# M206.net
KiCad netlist of a schematic drawn in EAGLE
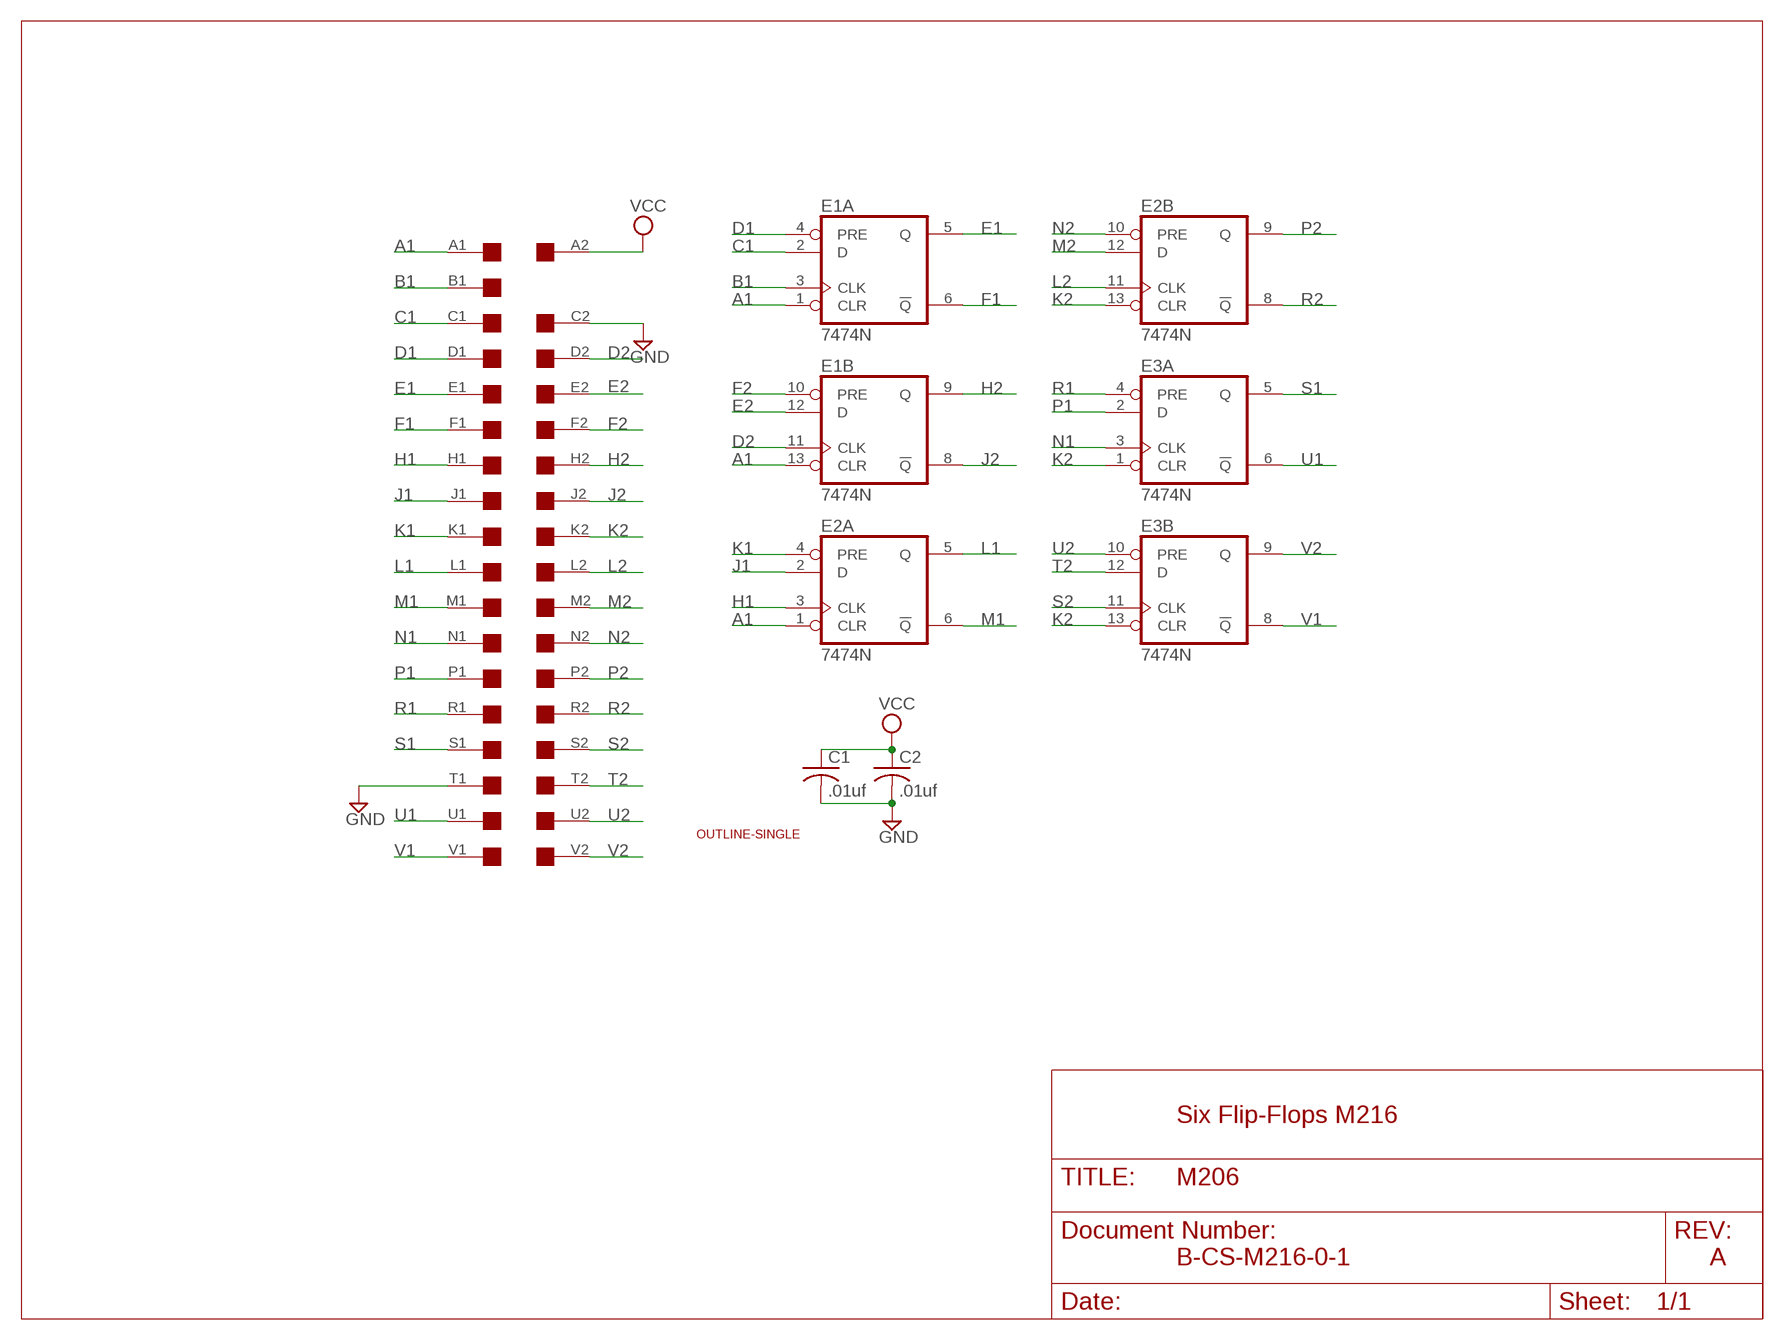
[diagram p0: schematic, sheet 1]

(export (version "E")
  (design (tool "Eeschema 10.0.6"))
  (components
    (comp (ref "C1")
      (value ".01uf")
      (footprint "eagle-import:C050-025X075")
      (libsource (lib "eagle-import") (part "C-US050-025X075"))
    )
    (comp (ref "C2")
      (value ".01uf")
      (footprint "eagle-import:C050-025X075")
      (libsource (lib "eagle-import") (part "C-US050-025X075"))
    )
    (comp (ref "E1")
      (value "7474N")
      (footprint "eagle-import:DIL14")
      (libsource (lib "eagle-import") (part "7474NS"))
    )
    (comp (ref "E2")
      (value "7474N")
      (footprint "eagle-import:DIL14")
      (libsource (lib "eagle-import") (part "7474NS"))
    )
    (comp (ref "E3")
      (value "7474N")
      (footprint "eagle-import:DIL14")
      (libsource (lib "eagle-import") (part "7474NS"))
    )
    (comp (ref "U$1")
      (value "OUTLINE-SINGLE")
      (footprint "eagle-import:SINGLE")
      (libsource (lib "eagle-import") (part "OUTLINE-SINGLE"))
    )
    (comp (ref "U$4")
      (value "SINGLE")
      (footprint "eagle-import:EDGE-CON2")
      (libsource (lib "eagle-import") (part "SINGLE"))
    )
  )
  (nets
    (net (code "1") (name "/A1") (class "Default")
      (node (ref "E1") (pin "1") (pinfunction "CLR_1") (pintype "input"))
      (node (ref "E1") (pin "13") (pinfunction "CLR_13") (pintype "input"))
      (node (ref "E2") (pin "1") (pinfunction "CLR_1") (pintype "input"))
      (node (ref "U$4") (pin "A1") (pinfunction "1_A1") (pintype "bidirectional"))
    )
    (net (code "2") (name "/B1") (class "Default")
      (node (ref "E1") (pin "3") (pinfunction "CLK_3") (pintype "input"))
      (node (ref "U$4") (pin "B1") (pinfunction "1_B1") (pintype "bidirectional"))
    )
    (net (code "3") (name "/C1") (class "Default")
      (node (ref "E1") (pin "2") (pinfunction "D_2") (pintype "input"))
      (node (ref "U$4") (pin "C1") (pinfunction "1_C1") (pintype "bidirectional"))
    )
    (net (code "4") (name "/D1") (class "Default")
      (node (ref "E1") (pin "4") (pinfunction "PRE_4") (pintype "input"))
      (node (ref "U$4") (pin "D1") (pinfunction "1_D1") (pintype "bidirectional"))
    )
    (net (code "5") (name "/D2") (class "Default")
      (node (ref "E1") (pin "11") (pinfunction "CLK_11") (pintype "input"))
      (node (ref "U$4") (pin "D2") (pinfunction "1_D2") (pintype "bidirectional"))
    )
    (net (code "6") (name "/E1") (class "Default")
      (node (ref "E1") (pin "5") (pinfunction "Q_5") (pintype "output"))
      (node (ref "U$4") (pin "E1") (pinfunction "1_E1") (pintype "bidirectional"))
    )
    (net (code "7") (name "/E2") (class "Default")
      (node (ref "E1") (pin "12") (pinfunction "D_12") (pintype "input"))
      (node (ref "U$4") (pin "E2") (pinfunction "1_E2") (pintype "bidirectional"))
    )
    (net (code "8") (name "/F1") (class "Default")
      (node (ref "E1") (pin "6") (pinfunction "~{Q}_6") (pintype "output"))
      (node (ref "U$4") (pin "F1") (pinfunction "1_F1") (pintype "bidirectional"))
    )
    (net (code "9") (name "/F2") (class "Default")
      (node (ref "E1") (pin "10") (pinfunction "PRE_10") (pintype "input"))
      (node (ref "U$4") (pin "F2") (pinfunction "1_F2") (pintype "bidirectional"))
    )
    (net (code "10") (name "/H1") (class "Default")
      (node (ref "E2") (pin "3") (pinfunction "CLK_3") (pintype "input"))
      (node (ref "U$4") (pin "H1") (pinfunction "1_H1") (pintype "bidirectional"))
    )
    (net (code "11") (name "/H2") (class "Default")
      (node (ref "E1") (pin "9") (pinfunction "Q_9") (pintype "output"))
      (node (ref "U$4") (pin "H2") (pinfunction "1_H2") (pintype "bidirectional"))
    )
    (net (code "12") (name "/J1") (class "Default")
      (node (ref "E2") (pin "2") (pinfunction "D_2") (pintype "input"))
      (node (ref "U$4") (pin "J1") (pinfunction "1_J1") (pintype "bidirectional"))
    )
    (net (code "13") (name "/J2") (class "Default")
      (node (ref "E1") (pin "8") (pinfunction "~{Q}_8") (pintype "output"))
      (node (ref "U$4") (pin "J2") (pinfunction "1_J2") (pintype "bidirectional"))
    )
    (net (code "14") (name "/K1") (class "Default")
      (node (ref "E2") (pin "4") (pinfunction "PRE_4") (pintype "input"))
      (node (ref "U$4") (pin "K1") (pinfunction "1_K1") (pintype "bidirectional"))
    )
    (net (code "15") (name "/K2") (class "Default")
      (node (ref "E2") (pin "13") (pinfunction "CLR_13") (pintype "input"))
      (node (ref "E3") (pin "1") (pinfunction "CLR_1") (pintype "input"))
      (node (ref "E3") (pin "13") (pinfunction "CLR_13") (pintype "input"))
      (node (ref "U$4") (pin "K2") (pinfunction "1_K2") (pintype "bidirectional"))
    )
    (net (code "16") (name "/L1") (class "Default")
      (node (ref "E2") (pin "5") (pinfunction "Q_5") (pintype "output"))
      (node (ref "U$4") (pin "L1") (pinfunction "1_L1") (pintype "bidirectional"))
    )
    (net (code "17") (name "/L2") (class "Default")
      (node (ref "E2") (pin "11") (pinfunction "CLK_11") (pintype "input"))
      (node (ref "U$4") (pin "L2") (pinfunction "1_L2") (pintype "bidirectional"))
    )
    (net (code "18") (name "/M1") (class "Default")
      (node (ref "E2") (pin "6") (pinfunction "~{Q}_6") (pintype "output"))
      (node (ref "U$4") (pin "M1") (pinfunction "1_M1") (pintype "bidirectional"))
    )
    (net (code "19") (name "/M2") (class "Default")
      (node (ref "E2") (pin "12") (pinfunction "D_12") (pintype "input"))
      (node (ref "U$4") (pin "M2") (pinfunction "1_M2") (pintype "bidirectional"))
    )
    (net (code "20") (name "/N1") (class "Default")
      (node (ref "E3") (pin "3") (pinfunction "CLK_3") (pintype "input"))
      (node (ref "U$4") (pin "N1") (pinfunction "1_N1") (pintype "bidirectional"))
    )
    (net (code "21") (name "/N2") (class "Default")
      (node (ref "E2") (pin "10") (pinfunction "PRE_10") (pintype "input"))
      (node (ref "U$4") (pin "N2") (pinfunction "1_N2") (pintype "bidirectional"))
    )
    (net (code "22") (name "/P1") (class "Default")
      (node (ref "E3") (pin "2") (pinfunction "D_2") (pintype "input"))
      (node (ref "U$4") (pin "P1") (pinfunction "1_P1") (pintype "bidirectional"))
    )
    (net (code "23") (name "/P2") (class "Default")
      (node (ref "E2") (pin "9") (pinfunction "Q_9") (pintype "output"))
      (node (ref "U$4") (pin "P2") (pinfunction "1_P2") (pintype "bidirectional"))
    )
    (net (code "24") (name "/R1") (class "Default")
      (node (ref "E3") (pin "4") (pinfunction "PRE_4") (pintype "input"))
      (node (ref "U$4") (pin "R1") (pinfunction "1_R1") (pintype "bidirectional"))
    )
    (net (code "25") (name "/R2") (class "Default")
      (node (ref "E2") (pin "8") (pinfunction "~{Q}_8") (pintype "output"))
      (node (ref "U$4") (pin "R2") (pinfunction "1_R2") (pintype "bidirectional"))
    )
    (net (code "26") (name "/S1") (class "Default")
      (node (ref "E3") (pin "5") (pinfunction "Q_5") (pintype "output"))
      (node (ref "U$4") (pin "S1") (pinfunction "1_S1") (pintype "bidirectional"))
    )
    (net (code "27") (name "/S2") (class "Default")
      (node (ref "E3") (pin "11") (pinfunction "CLK_11") (pintype "input"))
      (node (ref "U$4") (pin "S2") (pinfunction "1_S2") (pintype "bidirectional"))
    )
    (net (code "28") (name "/T2") (class "Default")
      (node (ref "E3") (pin "12") (pinfunction "D_12") (pintype "input"))
      (node (ref "U$4") (pin "T2") (pinfunction "1_T2") (pintype "bidirectional"))
    )
    (net (code "29") (name "/U1") (class "Default")
      (node (ref "E3") (pin "6") (pinfunction "~{Q}_6") (pintype "output"))
      (node (ref "U$4") (pin "U1") (pinfunction "1_U1") (pintype "bidirectional"))
    )
    (net (code "30") (name "/U2") (class "Default")
      (node (ref "E3") (pin "10") (pinfunction "PRE_10") (pintype "input"))
      (node (ref "U$4") (pin "U2") (pinfunction "1_U2") (pintype "bidirectional"))
    )
    (net (code "31") (name "/V1") (class "Default")
      (node (ref "E3") (pin "8") (pinfunction "~{Q}_8") (pintype "output"))
      (node (ref "U$4") (pin "V1") (pinfunction "1_V1") (pintype "bidirectional"))
    )
    (net (code "32") (name "/V2") (class "Default")
      (node (ref "E3") (pin "9") (pinfunction "Q_9") (pintype "output"))
      (node (ref "U$4") (pin "V2") (pinfunction "1_V2") (pintype "bidirectional"))
    )
    (net (code "33") (name "GND") (class "Default")
      (node (ref "C1") (pin "2") (pinfunction "2_2") (pintype "passive"))
      (node (ref "C2") (pin "2") (pinfunction "2_2") (pintype "passive"))
      (node (ref "U$4") (pin "C2") (pinfunction "1_C2") (pintype "bidirectional"))
      (node (ref "U$4") (pin "T1") (pinfunction "1_T1") (pintype "bidirectional"))
    )
    (net (code "34") (name "VCC") (class "Default")
      (node (ref "C1") (pin "1") (pinfunction "1_1") (pintype "passive"))
      (node (ref "C2") (pin "1") (pinfunction "1_1") (pintype "passive"))
      (node (ref "U$4") (pin "A2") (pinfunction "1_A2") (pintype "bidirectional"))
    )
  )
)
